# desticka.net
KiCad netlist of a schematic drawn in EAGLE
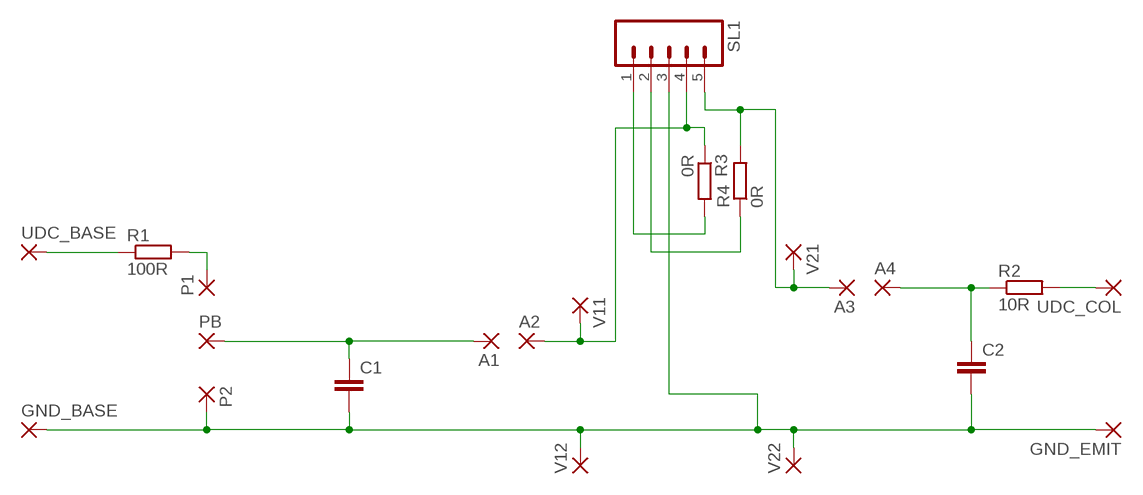
[diagram p0: schematic, sheet 1]

(export (version "E")
  (design (tool "Eeschema 10.0.6"))
  (components
    (comp (ref "A1")
      (value "3,17/1,3")
      (footprint "eagle-import:3,17_1,3")
      (libsource (lib "eagle-import") (part "3,17/1,3"))
    )
    (comp (ref "A2")
      (value "3,17/1,3")
      (footprint "eagle-import:3,17_1,3")
      (libsource (lib "eagle-import") (part "3,17/1,3"))
    )
    (comp (ref "A3")
      (value "3,17/1,3")
      (footprint "eagle-import:3,17_1,3")
      (libsource (lib "eagle-import") (part "3,17/1,3"))
    )
    (comp (ref "A4")
      (value "3,17/1,3")
      (footprint "eagle-import:3,17_1,3")
      (libsource (lib "eagle-import") (part "3,17/1,3"))
    )
    (comp (ref "C1")
      (value "C-EU050-055X075")
      (footprint "eagle-import:C050-055X075")
      (libsource (lib "eagle-import") (part "C-EU050-055X075"))
    )
    (comp (ref "C2")
      (value "C-EU050-055X075")
      (footprint "eagle-import:C050-055X075")
      (libsource (lib "eagle-import") (part "C-EU050-055X075"))
    )
    (comp (ref "GND_BASE")
      (value "3,17/1,3")
      (footprint "eagle-import:3,17_1,3")
      (libsource (lib "eagle-import") (part "3,17/1,3"))
    )
    (comp (ref "GND_EMIT")
      (value "3,17/1,3")
      (footprint "eagle-import:3,17_1,3")
      (libsource (lib "eagle-import") (part "3,17/1,3"))
    )
    (comp (ref "P1")
      (value "2,54/1,0")
      (footprint "eagle-import:2,54_1,0")
      (libsource (lib "eagle-import") (part "2,54/1,0"))
    )
    (comp (ref "P2")
      (value "2,54/1,0")
      (footprint "eagle-import:2,54_1,0")
      (libsource (lib "eagle-import") (part "2,54/1,0"))
    )
    (comp (ref "PB")
      (value "2,54/1,0")
      (footprint "eagle-import:2,54_1,0")
      (libsource (lib "eagle-import") (part "2,54/1,0"))
    )
    (comp (ref "R1")
      (value "100R")
      (footprint "eagle-import:P0613_15")
      (libsource (lib "eagle-import") (part "R-EU_0613/15"))
    )
    (comp (ref "R2")
      (value "10R")
      (footprint "eagle-import:P0613_15")
      (libsource (lib "eagle-import") (part "R-EU_0613/15"))
    )
    (comp (ref "R3")
      (value "0R")
      (footprint "eagle-import:0207_7")
      (libsource (lib "eagle-import") (part "R-EU_0207/7"))
    )
    (comp (ref "R4")
      (value "0R")
      (footprint "eagle-import:0207_7")
      (libsource (lib "eagle-import") (part "R-EU_0207/7"))
    )
    (comp (ref "SL1")
      (value "M05")
      (footprint "eagle-import:05P")
      (libsource (lib "eagle-import") (part "M05"))
    )
    (comp (ref "UDC_BASE")
      (value "3,17/1,3")
      (footprint "eagle-import:3,17_1,3")
      (libsource (lib "eagle-import") (part "3,17/1,3"))
    )
    (comp (ref "UDC_COL")
      (value "3,17/1,3")
      (footprint "eagle-import:3,17_1,3")
      (libsource (lib "eagle-import") (part "3,17/1,3"))
    )
    (comp (ref "V11")
      (value "3,17/1,3")
      (footprint "eagle-import:3,17_1,3")
      (libsource (lib "eagle-import") (part "3,17/1,3"))
    )
    (comp (ref "V12")
      (value "3,17/1,3")
      (footprint "eagle-import:3,17_1,3")
      (libsource (lib "eagle-import") (part "3,17/1,3"))
    )
    (comp (ref "V21")
      (value "3,17/1,3")
      (footprint "eagle-import:3,17_1,3")
      (libsource (lib "eagle-import") (part "3,17/1,3"))
    )
    (comp (ref "V22")
      (value "3,17/1,3")
      (footprint "eagle-import:3,17_1,3")
      (libsource (lib "eagle-import") (part "3,17/1,3"))
    )
  )
  (nets
    (net (code "1") (name "Net-(A1-P)") (class "Default")
      (node (ref "A1") (pin "1") (pinfunction "P_1") (pintype "passive"))
      (node (ref "C1") (pin "1") (pinfunction "1_1") (pintype "passive"))
      (node (ref "PB") (pin "1") (pinfunction "P_1") (pintype "passive"))
    )
    (net (code "2") (name "Net-(A2-P)") (class "Default")
      (node (ref "A2") (pin "1") (pinfunction "P_1") (pintype "passive"))
      (node (ref "R3") (pin "1") (pinfunction "1_1") (pintype "passive"))
      (node (ref "SL1") (pin "4") (pinfunction "4_4") (pintype "passive"))
      (node (ref "V11") (pin "1") (pinfunction "P_1") (pintype "passive"))
    )
    (net (code "3") (name "Net-(A3-P)") (class "Default")
      (node (ref "A3") (pin "1") (pinfunction "P_1") (pintype "passive"))
      (node (ref "R4") (pin "2") (pinfunction "2_2") (pintype "passive"))
      (node (ref "SL1") (pin "5") (pinfunction "5_5") (pintype "passive"))
      (node (ref "V21") (pin "1") (pinfunction "P_1") (pintype "passive"))
    )
    (net (code "4") (name "Net-(A4-P)") (class "Default")
      (node (ref "A4") (pin "1") (pinfunction "P_1") (pintype "passive"))
      (node (ref "C2") (pin "1") (pinfunction "1_1") (pintype "passive"))
      (node (ref "R2") (pin "1") (pinfunction "1_1") (pintype "passive"))
    )
    (net (code "5") (name "Net-(GND_BASE-P)") (class "Default")
      (node (ref "C1") (pin "2") (pinfunction "2_2") (pintype "passive"))
      (node (ref "C2") (pin "2") (pinfunction "2_2") (pintype "passive"))
      (node (ref "GND_BASE") (pin "1") (pinfunction "P_1") (pintype "passive"))
      (node (ref "GND_EMIT") (pin "1") (pinfunction "P_1") (pintype "passive"))
      (node (ref "P2") (pin "1") (pinfunction "P_1") (pintype "passive"))
      (node (ref "SL1") (pin "3") (pinfunction "3_3") (pintype "passive"))
      (node (ref "V12") (pin "1") (pinfunction "P_1") (pintype "passive"))
      (node (ref "V22") (pin "1") (pinfunction "P_1") (pintype "passive"))
    )
    (net (code "6") (name "Net-(P1-P)") (class "Default")
      (node (ref "P1") (pin "1") (pinfunction "P_1") (pintype "passive"))
      (node (ref "R1") (pin "2") (pinfunction "2_2") (pintype "passive"))
    )
    (net (code "7") (name "Net-(R3-Pad2)") (class "Default")
      (node (ref "R3") (pin "2") (pinfunction "2_2") (pintype "passive"))
      (node (ref "SL1") (pin "1") (pinfunction "1_1") (pintype "passive"))
    )
    (net (code "8") (name "Net-(R4-Pad1)") (class "Default")
      (node (ref "R4") (pin "1") (pinfunction "1_1") (pintype "passive"))
      (node (ref "SL1") (pin "2") (pinfunction "2_2") (pintype "passive"))
    )
    (net (code "9") (name "Net-(UDC_BASE-P)") (class "Default")
      (node (ref "R1") (pin "1") (pinfunction "1_1") (pintype "passive"))
      (node (ref "UDC_BASE") (pin "1") (pinfunction "P_1") (pintype "passive"))
    )
    (net (code "10") (name "Net-(UDC_COL-P)") (class "Default")
      (node (ref "R2") (pin "2") (pinfunction "2_2") (pintype "passive"))
      (node (ref "UDC_COL") (pin "1") (pinfunction "P_1") (pintype "passive"))
    )
  )
)
